# MyTouchPad.net
KiCad netlist of a schematic drawn in EasyEDA Pro
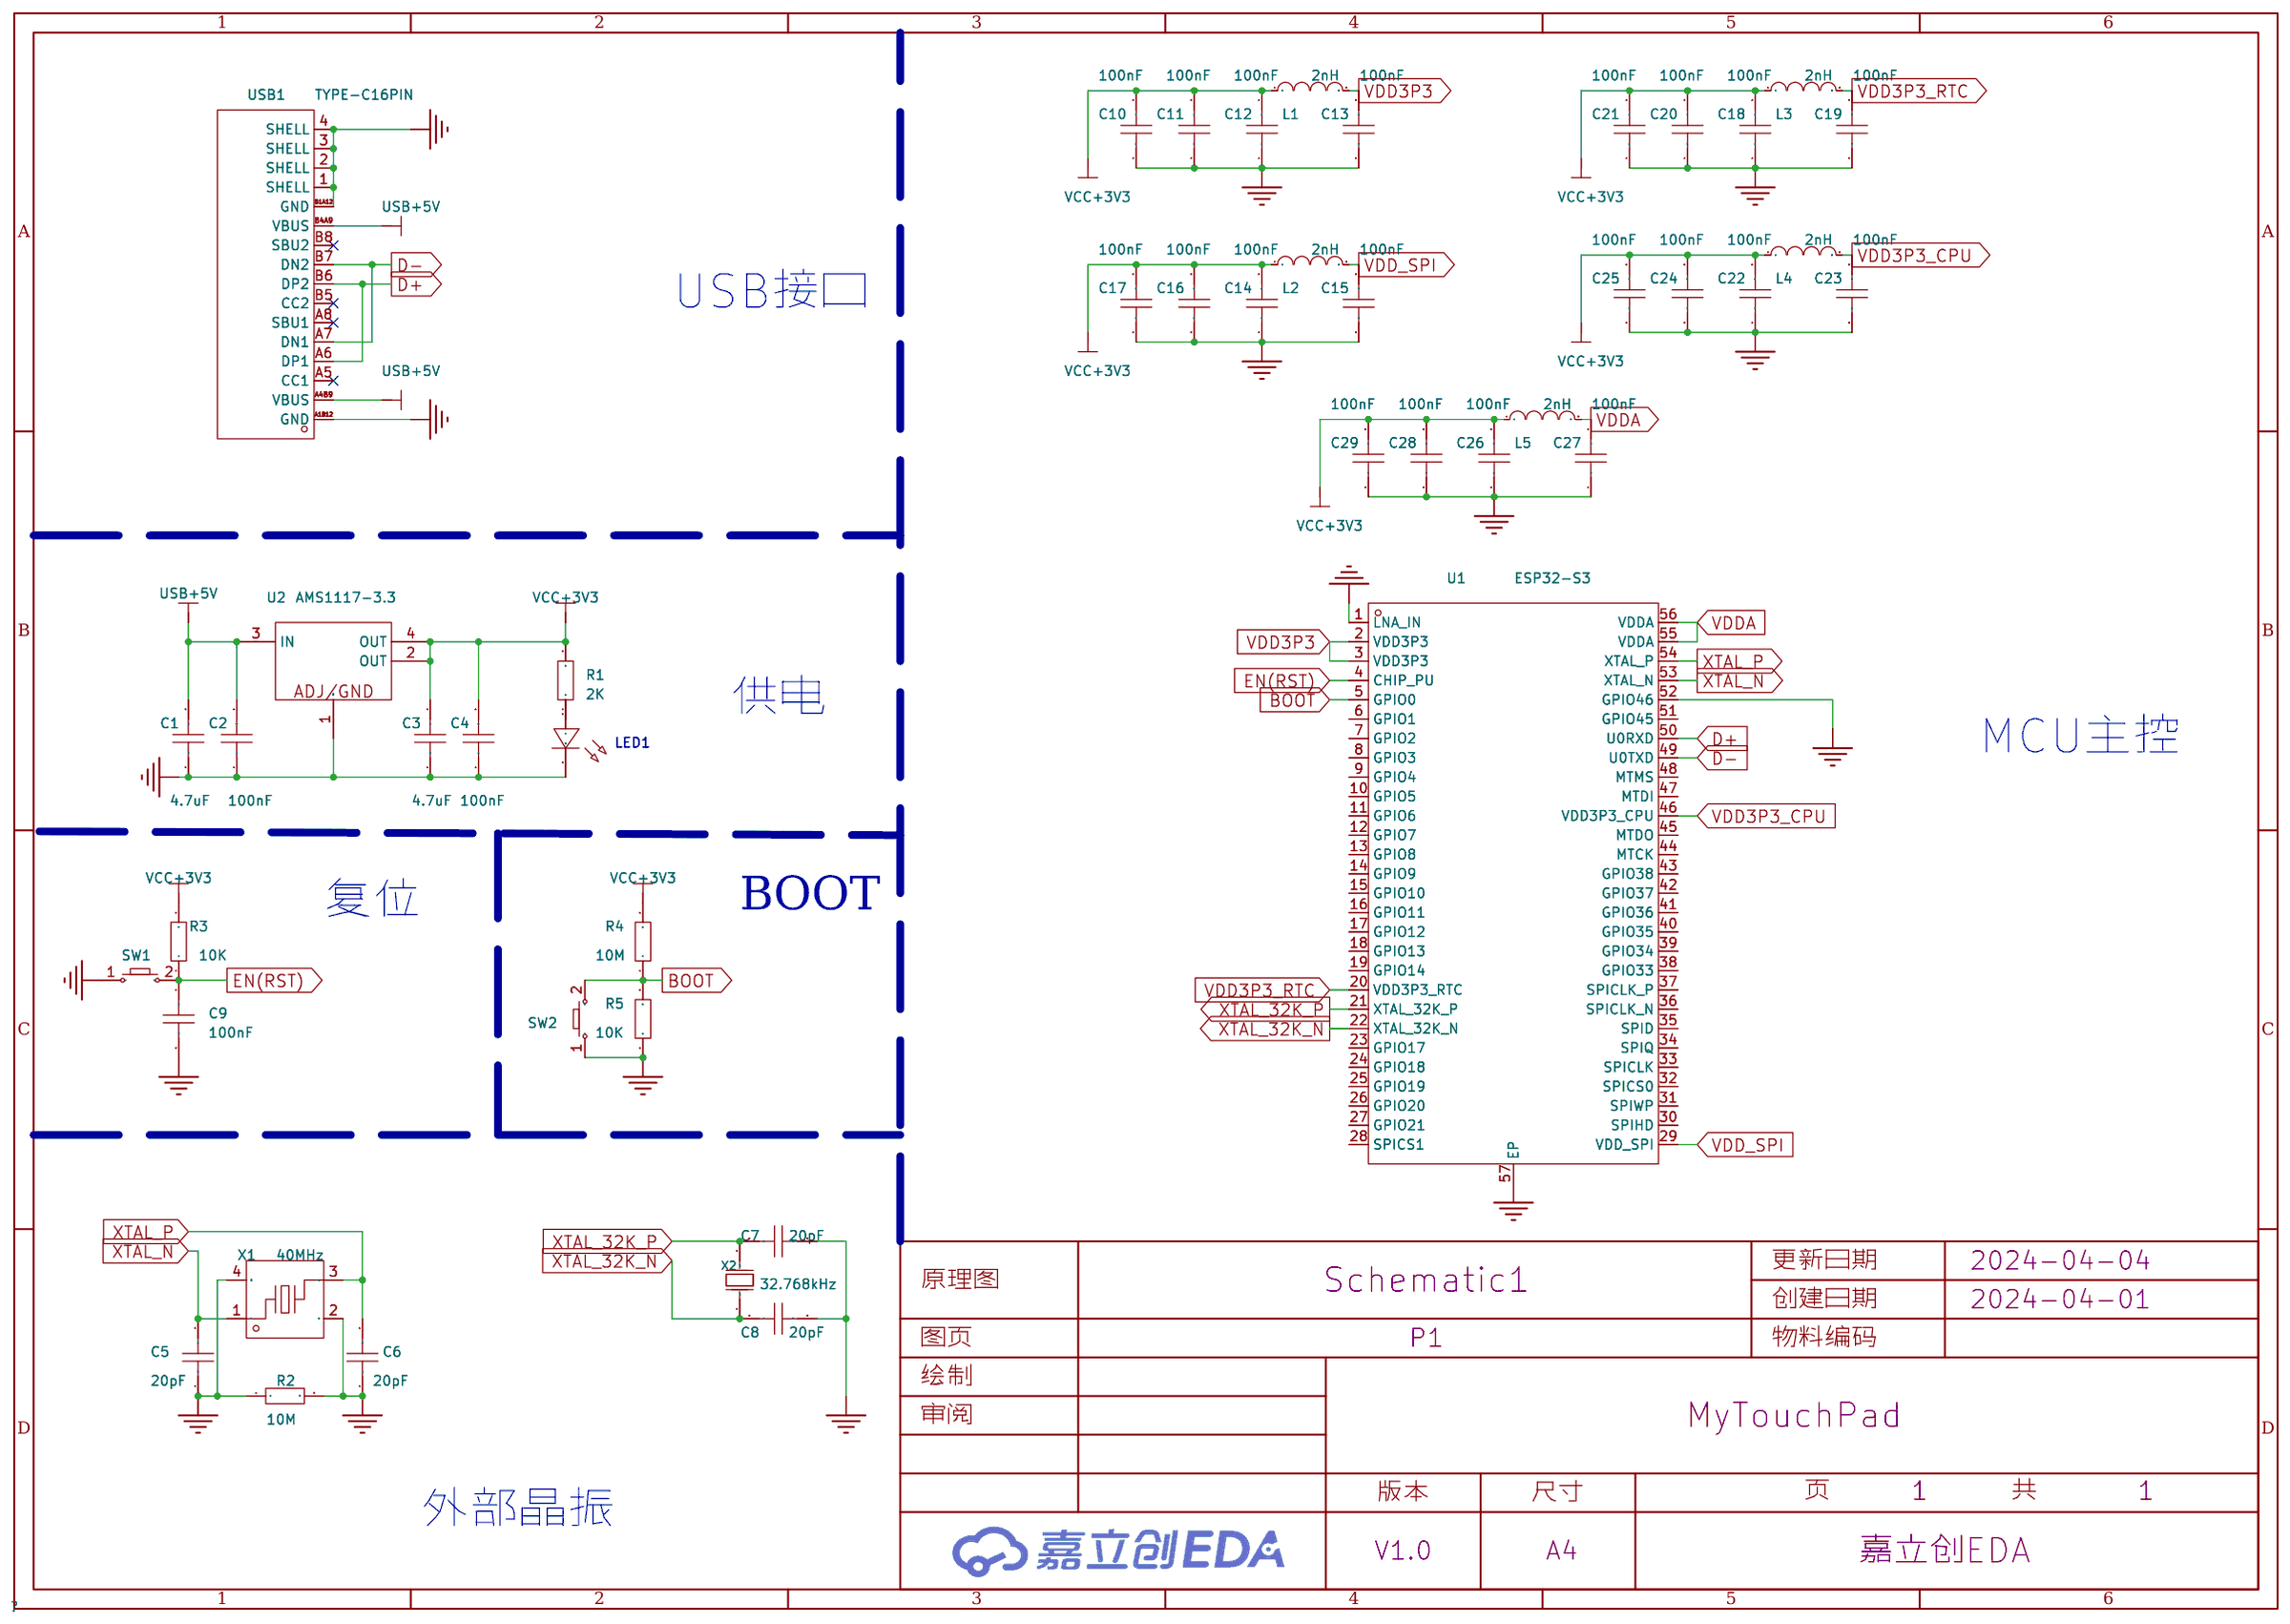
[diagram p0: schematic sheet]

(export (version "E")
  (design (tool "Eeschema 10.0.6"))
  (components
    (comp (ref "C1")
      (value "4.7uF")
      (footprint "easyedapro:C0603")
      (libsource (lib "easyedapro") (part "CapAcitance"))
    )
    (comp (ref "C2")
      (value "100nF")
      (footprint "easyedapro:C0603")
      (libsource (lib "easyedapro") (part "CapAcitance"))
    )
    (comp (ref "C3")
      (value "4.7uF")
      (footprint "easyedapro:C0603")
      (libsource (lib "easyedapro") (part "CapAcitance"))
    )
    (comp (ref "C4")
      (value "100nF")
      (footprint "easyedapro:C0603")
      (libsource (lib "easyedapro") (part "CapAcitance"))
    )
    (comp (ref "C5")
      (value "20pF")
      (footprint "easyedapro:C0603")
      (description "容值:20pF;精度:±2%;额定电压:50V;材质(温度系数):NP0;")
      (fields
        (field (name "Manufacturer Part") "CC0603GRNPO9BN200")
        (field (name "Manufacturer") "YAGEO(国巨)")
      )
      (libsource (lib "easyedapro") (part "CC0603GRNPO9BN200"))
    )
    (comp (ref "C6")
      (value "20pF")
      (footprint "easyedapro:C0603")
      (description "容值:20pF;精度:±2%;额定电压:50V;材质(温度系数):NP0;")
      (fields
        (field (name "Manufacturer Part") "CC0603GRNPO9BN200")
        (field (name "Manufacturer") "YAGEO(国巨)")
      )
      (libsource (lib "easyedapro") (part "CC0603GRNPO9BN200"))
    )
    (comp (ref "C7")
      (value "20pF")
      (footprint "easyedapro:C0603")
      (libsource (lib "easyedapro") (part "CapAcitance"))
    )
    (comp (ref "C8")
      (value "20pF")
      (footprint "easyedapro:C0603")
      (libsource (lib "easyedapro") (part "CapAcitance"))
    )
    (comp (ref "C9")
      (value "100nF")
      (footprint "easyedapro:C0603")
      (libsource (lib "easyedapro") (part "CapAcitance"))
    )
    (comp (ref "C10")
      (value "100nF")
      (footprint "easyedapro:C0603")
      (libsource (lib "easyedapro") (part "CapAcitance"))
    )
    (comp (ref "C11")
      (value "100nF")
      (footprint "easyedapro:C0603")
      (libsource (lib "easyedapro") (part "CapAcitance"))
    )
    (comp (ref "C12")
      (value "100nF")
      (footprint "easyedapro:C0603")
      (libsource (lib "easyedapro") (part "CapAcitance"))
    )
    (comp (ref "C13")
      (value "100nF")
      (footprint "easyedapro:C0603")
      (libsource (lib "easyedapro") (part "CapAcitance"))
    )
    (comp (ref "C14")
      (value "100nF")
      (footprint "easyedapro:C0603")
      (libsource (lib "easyedapro") (part "CapAcitance"))
    )
    (comp (ref "C15")
      (value "100nF")
      (footprint "easyedapro:C0603")
      (libsource (lib "easyedapro") (part "CapAcitance"))
    )
    (comp (ref "C16")
      (value "100nF")
      (footprint "easyedapro:C0603")
      (libsource (lib "easyedapro") (part "CapAcitance"))
    )
    (comp (ref "C17")
      (value "100nF")
      (footprint "easyedapro:C0603")
      (libsource (lib "easyedapro") (part "CapAcitance"))
    )
    (comp (ref "C18")
      (value "100nF")
      (footprint "easyedapro:C0603")
      (libsource (lib "easyedapro") (part "CapAcitance"))
    )
    (comp (ref "C19")
      (value "100nF")
      (footprint "easyedapro:C0603")
      (libsource (lib "easyedapro") (part "CapAcitance"))
    )
    (comp (ref "C20")
      (value "100nF")
      (footprint "easyedapro:C0603")
      (libsource (lib "easyedapro") (part "CapAcitance"))
    )
    (comp (ref "C21")
      (value "100nF")
      (footprint "easyedapro:C0603")
      (libsource (lib "easyedapro") (part "CapAcitance"))
    )
    (comp (ref "C22")
      (value "100nF")
      (footprint "easyedapro:C0603")
      (libsource (lib "easyedapro") (part "CapAcitance"))
    )
    (comp (ref "C23")
      (value "100nF")
      (footprint "easyedapro:C0603")
      (libsource (lib "easyedapro") (part "CapAcitance"))
    )
    (comp (ref "C24")
      (value "100nF")
      (footprint "easyedapro:C0603")
      (libsource (lib "easyedapro") (part "CapAcitance"))
    )
    (comp (ref "C25")
      (value "100nF")
      (footprint "easyedapro:C0603")
      (libsource (lib "easyedapro") (part "CapAcitance"))
    )
    (comp (ref "C26")
      (value "100nF")
      (footprint "easyedapro:C0603")
      (libsource (lib "easyedapro") (part "CapAcitance"))
    )
    (comp (ref "C27")
      (value "100nF")
      (footprint "easyedapro:C0603")
      (libsource (lib "easyedapro") (part "CapAcitance"))
    )
    (comp (ref "C28")
      (value "100nF")
      (footprint "easyedapro:C0603")
      (libsource (lib "easyedapro") (part "CapAcitance"))
    )
    (comp (ref "C29")
      (value "100nF")
      (footprint "easyedapro:C0603")
      (libsource (lib "easyedapro") (part "CapAcitance"))
    )
    (comp (ref "L1")
      (value "2nH")
      (footprint "easyedapro:L0603")
      (libsource (lib "easyedapro") (part "SDFL1608S100KTF"))
    )
    (comp (ref "L2")
      (value "2nH")
      (footprint "easyedapro:L0603")
      (libsource (lib "easyedapro") (part "SDFL1608S100KTF"))
    )
    (comp (ref "L3")
      (value "2nH")
      (footprint "easyedapro:L0603")
      (libsource (lib "easyedapro") (part "SDFL1608S100KTF"))
    )
    (comp (ref "L4")
      (value "2nH")
      (footprint "easyedapro:L0603")
      (libsource (lib "easyedapro") (part "SDFL1608S100KTF"))
    )
    (comp (ref "L5")
      (value "2nH")
      (footprint "easyedapro:L0603")
      (libsource (lib "easyedapro") (part "SDFL1608S100KTF"))
    )
    (comp (ref "LED1")
      (value "~")
      (footprint "easyedapro:LED_0603")
      (libsource (lib "easyedapro") (part "LED_G"))
    )
    (comp (ref "R1") (value "2K") (footprint "easyedapro:R0603") (libsource (lib "easyedapro") (part "电阻")))
    (comp (ref "R2") (value "10M") (footprint "easyedapro:R0603") (libsource (lib "easyedapro") (part "电阻")))
    (comp (ref "R3") (value "10K") (footprint "easyedapro:R0603") (libsource (lib "easyedapro") (part "电阻")))
    (comp (ref "R4") (value "10M") (footprint "easyedapro:R0603") (libsource (lib "easyedapro") (part "电阻")))
    (comp (ref "R5") (value "10K") (footprint "easyedapro:R0603") (libsource (lib "easyedapro") (part "电阻")))
    (comp (ref "SW1")
      (value "~")
      (footprint "easyedapro:Key_SMD_3x4x2")
      (libsource (lib "easyedapro") (part "轻触按键x2"))
    )
    (comp (ref "SW2")
      (value "~")
      (footprint "easyedapro:Key_SMD_3x4x2")
      (libsource (lib "easyedapro") (part "轻触按键x2"))
    )
    (comp (ref "U1")
      (value "ESP32-S3")
      (footprint "easyedapro:QFN-56_L7.0-W7.0-P0.40-TL-EP4.0")
      (fields (field (name "Manufacturer") "ESPRESSIF(乐鑫)"))
      (libsource (lib "easyedapro") (part "ESP32-S3"))
    )
    (comp (ref "U2")
      (value "AMS1117-3.3")
      (footprint "easyedapro:SOT-223-3_L6.4-W3.5-P2.30-LS7.0-BR")
      (fields (field (name "Manufacturer") "国芯佳品"))
      (libsource (lib "easyedapro") (part "AMS1117-3.3_C2992570"))
    )
    (comp (ref "USB1")
      (value "TYPE-C16PIN")
      (footprint "easyedapro:USB-C-SMD_TYPE-C16PIN")
      (description "连接器类型:Type-C;标准:-;公母:母;端口数量:1;触点数量:16P;安装方式:卧贴;额定电流 - 电源:3A;工作温度范围:-40°C~+85°C;")
      (fields (field (name "Manufacturer") "SHOU HAN(首韩)"))
      (libsource (lib "easyedapro") (part "TYPE-C16PIN"))
    )
    (comp (ref "X1")
      (value "40MHz")
      (footprint "easyedapro:CRYSTAL-SMD_4P-L2.5-W2.0-BL")
      (description "晶振类型:贴片晶振;频率:40MHz;常温频差:±10ppm;外接负载电容:9pF;")
      (fields (field (name "Manufacturer Part") "S2240000091050JY") (field (name "Manufacturer") "JGHC(晶光华)"))
      (libsource (lib "easyedapro") (part "S2240000091050JY"))
    )
    (comp (ref "X2")
      (value "32.768kHz")
      (footprint "easyedapro:CRYSTAL-SMD_L3.2-W1.5-2")
      (description "频率:32.768kHz;常温频差:±20ppm;外接负载电容:6pF;频率稳定度(全温):-;")
      (fields
        (field (name "Manufacturer Part") "ABS07-32.768KHZ-6-T")
        (field (name "Manufacturer") "ABRACON")
      )
      (libsource (lib "easyedapro") (part "ABS07-32.768KHZ-6-T"))
    )
  )
  (nets
    (net (code "1") (name "BOOT") (class "Default")
      (node (ref "R4") (pin "1") (pinfunction "1_1") (pintype "input"))
      (node (ref "R5") (pin "2") (pinfunction "2_2") (pintype "input"))
      (node (ref "SW2") (pin "2") (pinfunction "2_2") (pintype "input"))
      (node (ref "U1") (pin "5") (pinfunction "GPIO0_5") (pintype "unspecified"))
    )
    (net (code "2") (name "D+") (class "Default")
      (node (ref "U1") (pin "50") (pinfunction "U0RXD_50") (pintype "unspecified"))
      (node (ref "USB1") (pin "A6") (pinfunction "DP1_A6") (pintype "unspecified"))
      (node (ref "USB1") (pin "B6") (pinfunction "DP2_B6") (pintype "unspecified"))
    )
    (net (code "3") (name "D-") (class "Default")
      (node (ref "U1") (pin "49") (pinfunction "U0TXD_49") (pintype "unspecified"))
      (node (ref "USB1") (pin "A7") (pinfunction "DN1_A7") (pintype "unspecified"))
      (node (ref "USB1") (pin "B7") (pinfunction "DN2_B7") (pintype "unspecified"))
    )
    (net (code "4") (name "EN(RST)") (class "Default")
      (node (ref "C9") (pin "1") (pinfunction "1_1") (pintype "input"))
      (node (ref "R3") (pin "1") (pinfunction "1_1") (pintype "input"))
      (node (ref "SW1") (pin "2") (pinfunction "2_2") (pintype "input"))
      (node (ref "U1") (pin "4") (pinfunction "CHIP_PU_4") (pintype "unspecified"))
    )
    (net (code "5") (name "GND") (class "Default")
      (node (ref "C1") (pin "1") (pinfunction "1_1") (pintype "input"))
      (node (ref "C10") (pin "1") (pinfunction "1_1") (pintype "input"))
      (node (ref "C11") (pin "1") (pinfunction "1_1") (pintype "input"))
      (node (ref "C12") (pin "1") (pinfunction "1_1") (pintype "input"))
      (node (ref "C13") (pin "1") (pinfunction "1_1") (pintype "input"))
      (node (ref "C14") (pin "1") (pinfunction "1_1") (pintype "input"))
      (node (ref "C15") (pin "1") (pinfunction "1_1") (pintype "input"))
      (node (ref "C16") (pin "1") (pinfunction "1_1") (pintype "input"))
      (node (ref "C17") (pin "1") (pinfunction "1_1") (pintype "input"))
      (node (ref "C18") (pin "1") (pinfunction "1_1") (pintype "input"))
      (node (ref "C19") (pin "1") (pinfunction "1_1") (pintype "input"))
      (node (ref "C2") (pin "1") (pinfunction "1_1") (pintype "input"))
      (node (ref "C20") (pin "1") (pinfunction "1_1") (pintype "input"))
      (node (ref "C21") (pin "1") (pinfunction "1_1") (pintype "input"))
      (node (ref "C22") (pin "1") (pinfunction "1_1") (pintype "input"))
      (node (ref "C23") (pin "1") (pinfunction "1_1") (pintype "input"))
      (node (ref "C24") (pin "1") (pinfunction "1_1") (pintype "input"))
      (node (ref "C25") (pin "1") (pinfunction "1_1") (pintype "input"))
      (node (ref "C26") (pin "1") (pinfunction "1_1") (pintype "input"))
      (node (ref "C27") (pin "1") (pinfunction "1_1") (pintype "input"))
      (node (ref "C28") (pin "1") (pinfunction "1_1") (pintype "input"))
      (node (ref "C29") (pin "1") (pinfunction "1_1") (pintype "input"))
      (node (ref "C3") (pin "1") (pinfunction "1_1") (pintype "input"))
      (node (ref "C4") (pin "1") (pinfunction "1_1") (pintype "input"))
      (node (ref "C5") (pin "1") (pinfunction "1_1") (pintype "unspecified"))
      (node (ref "C6") (pin "1") (pinfunction "1_1") (pintype "unspecified"))
      (node (ref "C7") (pin "2") (pinfunction "2_2") (pintype "input"))
      (node (ref "C8") (pin "2") (pinfunction "2_2") (pintype "input"))
      (node (ref "C9") (pin "2") (pinfunction "2_2") (pintype "input"))
      (node (ref "LED1") (pin "1") (pinfunction "C_1") (pintype "input"))
      (node (ref "R2") (pin "1") (pinfunction "1_1") (pintype "input"))
      (node (ref "R2") (pin "2") (pinfunction "2_2") (pintype "input"))
      (node (ref "R5") (pin "1") (pinfunction "1_1") (pintype "input"))
      (node (ref "SW1") (pin "1") (pinfunction "1_1") (pintype "input"))
      (node (ref "SW2") (pin "1") (pinfunction "1_1") (pintype "input"))
      (node (ref "U1") (pin "1") (pinfunction "LNA_IN_1") (pintype "unspecified"))
      (node (ref "U1") (pin "52") (pinfunction "GPIO46_52") (pintype "unspecified"))
      (node (ref "U1") (pin "57") (pinfunction "EP_57") (pintype "unspecified"))
      (node (ref "U2") (pin "1") (pinfunction "ADJ/GND_1") (pintype "unspecified"))
      (node (ref "USB1") (pin "1") (pinfunction "SHELL_1") (pintype "unspecified"))
      (node (ref "USB1") (pin "2") (pinfunction "SHELL_2") (pintype "unspecified"))
      (node (ref "USB1") (pin "3") (pinfunction "SHELL_3") (pintype "unspecified"))
      (node (ref "USB1") (pin "4") (pinfunction "SHELL_4") (pintype "unspecified"))
      (node (ref "USB1") (pin "A1B12") (pinfunction "GND_A1B12") (pintype "unspecified"))
      (node (ref "USB1") (pin "B1A12") (pinfunction "GND_B1A12") (pintype "unspecified"))
      (node (ref "X1") (pin "2") (pinfunction "GND_2") (pintype "input"))
      (node (ref "X1") (pin "4") (pinfunction "GND_4") (pintype "input"))
    )
    (net (code "6") (name "Net-(LED1-A)") (class "Default")
      (node (ref "LED1") (pin "2") (pinfunction "A_2") (pintype "input"))
      (node (ref "R1") (pin "1") (pinfunction "1_1") (pintype "input"))
    )
    (net (code "7") (name "USB+5V") (class "Default")
      (node (ref "C1") (pin "2") (pinfunction "2_2") (pintype "input"))
      (node (ref "C2") (pin "2") (pinfunction "2_2") (pintype "input"))
      (node (ref "U2") (pin "3") (pinfunction "IN_3") (pintype "unspecified"))
      (node (ref "USB1") (pin "A4B9") (pinfunction "VBUS_A4B9") (pintype "unspecified"))
      (node (ref "USB1") (pin "B4A9") (pinfunction "VBUS_B4A9") (pintype "unspecified"))
    )
    (net (code "8") (name "VCC+3V3") (class "Default")
      (node (ref "C10") (pin "2") (pinfunction "2_2") (pintype "input"))
      (node (ref "C11") (pin "2") (pinfunction "2_2") (pintype "input"))
      (node (ref "C12") (pin "2") (pinfunction "2_2") (pintype "input"))
      (node (ref "C14") (pin "2") (pinfunction "2_2") (pintype "input"))
      (node (ref "C16") (pin "2") (pinfunction "2_2") (pintype "input"))
      (node (ref "C17") (pin "2") (pinfunction "2_2") (pintype "input"))
      (node (ref "C18") (pin "2") (pinfunction "2_2") (pintype "input"))
      (node (ref "C20") (pin "2") (pinfunction "2_2") (pintype "input"))
      (node (ref "C21") (pin "2") (pinfunction "2_2") (pintype "input"))
      (node (ref "C22") (pin "2") (pinfunction "2_2") (pintype "input"))
      (node (ref "C24") (pin "2") (pinfunction "2_2") (pintype "input"))
      (node (ref "C25") (pin "2") (pinfunction "2_2") (pintype "input"))
      (node (ref "C26") (pin "2") (pinfunction "2_2") (pintype "input"))
      (node (ref "C28") (pin "2") (pinfunction "2_2") (pintype "input"))
      (node (ref "C29") (pin "2") (pinfunction "2_2") (pintype "input"))
      (node (ref "C3") (pin "2") (pinfunction "2_2") (pintype "input"))
      (node (ref "C4") (pin "2") (pinfunction "2_2") (pintype "input"))
      (node (ref "L1") (pin "1") (pinfunction "1_1") (pintype "unspecified"))
      (node (ref "L2") (pin "1") (pinfunction "1_1") (pintype "unspecified"))
      (node (ref "L3") (pin "1") (pinfunction "1_1") (pintype "unspecified"))
      (node (ref "L4") (pin "1") (pinfunction "1_1") (pintype "unspecified"))
      (node (ref "L5") (pin "1") (pinfunction "1_1") (pintype "unspecified"))
      (node (ref "R1") (pin "2") (pinfunction "2_2") (pintype "input"))
      (node (ref "R3") (pin "2") (pinfunction "2_2") (pintype "input"))
      (node (ref "R4") (pin "2") (pinfunction "2_2") (pintype "input"))
      (node (ref "U2") (pin "2") (pinfunction "OUT_2") (pintype "unspecified"))
      (node (ref "U2") (pin "4") (pinfunction "OUT_4") (pintype "unspecified"))
    )
    (net (code "9") (name "VDD3P3") (class "Default")
      (node (ref "C13") (pin "2") (pinfunction "2_2") (pintype "input"))
      (node (ref "L1") (pin "2") (pinfunction "2_2") (pintype "unspecified"))
      (node (ref "U1") (pin "2") (pinfunction "VDD3P3_2") (pintype "unspecified"))
      (node (ref "U1") (pin "3") (pinfunction "VDD3P3_3") (pintype "unspecified"))
    )
    (net (code "10") (name "VDD3P3_CPU") (class "Default")
      (node (ref "C23") (pin "2") (pinfunction "2_2") (pintype "input"))
      (node (ref "L4") (pin "2") (pinfunction "2_2") (pintype "unspecified"))
      (node (ref "U1") (pin "46") (pinfunction "VDD3P3_CPU_46") (pintype "unspecified"))
    )
    (net (code "11") (name "VDD3P3_RTC") (class "Default")
      (node (ref "C19") (pin "2") (pinfunction "2_2") (pintype "input"))
      (node (ref "L3") (pin "2") (pinfunction "2_2") (pintype "unspecified"))
      (node (ref "U1") (pin "20") (pinfunction "VDD3P3_RTC_20") (pintype "unspecified"))
    )
    (net (code "12") (name "VDDA") (class "Default")
      (node (ref "C27") (pin "2") (pinfunction "2_2") (pintype "input"))
      (node (ref "L5") (pin "2") (pinfunction "2_2") (pintype "unspecified"))
      (node (ref "U1") (pin "55") (pinfunction "VDDA_55") (pintype "unspecified"))
      (node (ref "U1") (pin "56") (pinfunction "VDDA_56") (pintype "unspecified"))
    )
    (net (code "13") (name "VDD_SPI") (class "Default")
      (node (ref "C15") (pin "2") (pinfunction "2_2") (pintype "input"))
      (node (ref "L2") (pin "2") (pinfunction "2_2") (pintype "unspecified"))
      (node (ref "U1") (pin "29") (pinfunction "VDD_SPI_29") (pintype "unspecified"))
    )
    (net (code "14") (name "XTAL_32K_N") (class "Default")
      (node (ref "C8") (pin "1") (pinfunction "1_1") (pintype "input"))
      (node (ref "U1") (pin "22") (pinfunction "XTAL_32K_N_22") (pintype "unspecified"))
      (node (ref "X2") (pin "1") (pinfunction "OSC1_1") (pintype "input"))
    )
    (net (code "15") (name "XTAL_32K_P") (class "Default")
      (node (ref "C7") (pin "1") (pinfunction "1_1") (pintype "input"))
      (node (ref "U1") (pin "21") (pinfunction "XTAL_32K_P_21") (pintype "unspecified"))
      (node (ref "X2") (pin "2") (pinfunction "OSC2_2") (pintype "input"))
    )
    (net (code "16") (name "XTAL_N") (class "Default")
      (node (ref "C5") (pin "2") (pinfunction "2_2") (pintype "unspecified"))
      (node (ref "U1") (pin "53") (pinfunction "XTAL_N_53") (pintype "unspecified"))
      (node (ref "X1") (pin "1") (pinfunction "1_1") (pintype "input"))
    )
    (net (code "17") (name "XTAL_P") (class "Default")
      (node (ref "C6") (pin "2") (pinfunction "2_2") (pintype "unspecified"))
      (node (ref "U1") (pin "54") (pinfunction "XTAL_P_54") (pintype "unspecified"))
      (node (ref "X1") (pin "3") (pinfunction "3_3") (pintype "input"))
    )
    (net (code "18") (name "unconnected-(U1-GPIO1-Pad6)") (class "Default")
      (node (ref "U1") (pin "6") (pinfunction "GPIO1_6") (pintype "unspecified"))
    )
    (net (code "19") (name "unconnected-(U1-GPIO2-Pad7)") (class "Default")
      (node (ref "U1") (pin "7") (pinfunction "GPIO2_7") (pintype "unspecified"))
    )
    (net (code "20") (name "unconnected-(U1-GPIO3-Pad8)") (class "Default")
      (node (ref "U1") (pin "8") (pinfunction "GPIO3_8") (pintype "unspecified"))
    )
    (net (code "21") (name "unconnected-(U1-GPIO4-Pad9)") (class "Default")
      (node (ref "U1") (pin "9") (pinfunction "GPIO4_9") (pintype "unspecified"))
    )
    (net (code "22") (name "unconnected-(U1-GPIO5-Pad10)") (class "Default")
      (node (ref "U1") (pin "10") (pinfunction "GPIO5_10") (pintype "unspecified"))
    )
    (net (code "23") (name "unconnected-(U1-GPIO6-Pad11)") (class "Default")
      (node (ref "U1") (pin "11") (pinfunction "GPIO6_11") (pintype "unspecified"))
    )
    (net (code "24") (name "unconnected-(U1-GPIO7-Pad12)") (class "Default")
      (node (ref "U1") (pin "12") (pinfunction "GPIO7_12") (pintype "unspecified"))
    )
    (net (code "25") (name "unconnected-(U1-GPIO8-Pad13)") (class "Default")
      (node (ref "U1") (pin "13") (pinfunction "GPIO8_13") (pintype "unspecified"))
    )
    (net (code "26") (name "unconnected-(U1-GPIO9-Pad14)") (class "Default")
      (node (ref "U1") (pin "14") (pinfunction "GPIO9_14") (pintype "unspecified"))
    )
    (net (code "27") (name "unconnected-(U1-GPIO10-Pad15)") (class "Default")
      (node (ref "U1") (pin "15") (pinfunction "GPIO10_15") (pintype "unspecified"))
    )
    (net (code "28") (name "unconnected-(U1-GPIO11-Pad16)") (class "Default")
      (node (ref "U1") (pin "16") (pinfunction "GPIO11_16") (pintype "unspecified"))
    )
    (net (code "29") (name "unconnected-(U1-GPIO12-Pad17)") (class "Default")
      (node (ref "U1") (pin "17") (pinfunction "GPIO12_17") (pintype "unspecified"))
    )
    (net (code "30") (name "unconnected-(U1-GPIO13-Pad18)") (class "Default")
      (node (ref "U1") (pin "18") (pinfunction "GPIO13_18") (pintype "unspecified"))
    )
    (net (code "31") (name "unconnected-(U1-GPIO14-Pad19)") (class "Default")
      (node (ref "U1") (pin "19") (pinfunction "GPIO14_19") (pintype "unspecified"))
    )
    (net (code "32") (name "unconnected-(U1-GPIO17-Pad23)") (class "Default")
      (node (ref "U1") (pin "23") (pinfunction "GPIO17_23") (pintype "unspecified"))
    )
    (net (code "33") (name "unconnected-(U1-GPIO18-Pad24)") (class "Default")
      (node (ref "U1") (pin "24") (pinfunction "GPIO18_24") (pintype "unspecified"))
    )
    (net (code "34") (name "unconnected-(U1-GPIO19-Pad25)") (class "Default")
      (node (ref "U1") (pin "25") (pinfunction "GPIO19_25") (pintype "unspecified"))
    )
    (net (code "35") (name "unconnected-(U1-GPIO20-Pad26)") (class "Default")
      (node (ref "U1") (pin "26") (pinfunction "GPIO20_26") (pintype "unspecified"))
    )
    (net (code "36") (name "unconnected-(U1-GPIO21-Pad27)") (class "Default")
      (node (ref "U1") (pin "27") (pinfunction "GPIO21_27") (pintype "unspecified"))
    )
    (net (code "37") (name "unconnected-(U1-GPIO33-Pad38)") (class "Default")
      (node (ref "U1") (pin "38") (pinfunction "GPIO33_38") (pintype "unspecified"))
    )
    (net (code "38") (name "unconnected-(U1-GPIO34-Pad39)") (class "Default")
      (node (ref "U1") (pin "39") (pinfunction "GPIO34_39") (pintype "unspecified"))
    )
    (net (code "39") (name "unconnected-(U1-GPIO35-Pad40)") (class "Default")
      (node (ref "U1") (pin "40") (pinfunction "GPIO35_40") (pintype "unspecified"))
    )
    (net (code "40") (name "unconnected-(U1-GPIO36-Pad41)") (class "Default")
      (node (ref "U1") (pin "41") (pinfunction "GPIO36_41") (pintype "unspecified"))
    )
    (net (code "41") (name "unconnected-(U1-GPIO37-Pad42)") (class "Default")
      (node (ref "U1") (pin "42") (pinfunction "GPIO37_42") (pintype "unspecified"))
    )
    (net (code "42") (name "unconnected-(U1-GPIO38-Pad43)") (class "Default")
      (node (ref "U1") (pin "43") (pinfunction "GPIO38_43") (pintype "unspecified"))
    )
    (net (code "43") (name "unconnected-(U1-GPIO45-Pad51)") (class "Default")
      (node (ref "U1") (pin "51") (pinfunction "GPIO45_51") (pintype "unspecified"))
    )
    (net (code "44") (name "unconnected-(U1-MTCK-Pad44)") (class "Default")
      (node (ref "U1") (pin "44") (pinfunction "MTCK_44") (pintype "unspecified"))
    )
    (net (code "45") (name "unconnected-(U1-MTDI-Pad47)") (class "Default")
      (node (ref "U1") (pin "47") (pinfunction "MTDI_47") (pintype "unspecified"))
    )
    (net (code "46") (name "unconnected-(U1-MTDO-Pad45)") (class "Default")
      (node (ref "U1") (pin "45") (pinfunction "MTDO_45") (pintype "unspecified"))
    )
    (net (code "47") (name "unconnected-(U1-MTMS-Pad48)") (class "Default")
      (node (ref "U1") (pin "48") (pinfunction "MTMS_48") (pintype "unspecified"))
    )
    (net (code "48") (name "unconnected-(U1-SPICLK-Pad33)") (class "Default")
      (node (ref "U1") (pin "33") (pinfunction "SPICLK_33") (pintype "unspecified"))
    )
    (net (code "49") (name "unconnected-(U1-SPICLK_N-Pad36)") (class "Default")
      (node (ref "U1") (pin "36") (pinfunction "SPICLK_N_36") (pintype "unspecified"))
    )
    (net (code "50") (name "unconnected-(U1-SPICLK_P-Pad37)") (class "Default")
      (node (ref "U1") (pin "37") (pinfunction "SPICLK_P_37") (pintype "unspecified"))
    )
    (net (code "51") (name "unconnected-(U1-SPICS0-Pad32)") (class "Default")
      (node (ref "U1") (pin "32") (pinfunction "SPICS0_32") (pintype "unspecified"))
    )
    (net (code "52") (name "unconnected-(U1-SPICS1-Pad28)") (class "Default")
      (node (ref "U1") (pin "28") (pinfunction "SPICS1_28") (pintype "unspecified"))
    )
    (net (code "53") (name "unconnected-(U1-SPID-Pad35)") (class "Default")
      (node (ref "U1") (pin "35") (pinfunction "SPID_35") (pintype "unspecified"))
    )
    (net (code "54") (name "unconnected-(U1-SPIHD-Pad30)") (class "Default")
      (node (ref "U1") (pin "30") (pinfunction "SPIHD_30") (pintype "unspecified"))
    )
    (net (code "55") (name "unconnected-(U1-SPIQ-Pad34)") (class "Default")
      (node (ref "U1") (pin "34") (pinfunction "SPIQ_34") (pintype "unspecified"))
    )
    (net (code "56") (name "unconnected-(U1-SPIWP-Pad31)") (class "Default")
      (node (ref "U1") (pin "31") (pinfunction "SPIWP_31") (pintype "unspecified"))
    )
    (net (code "57") (name "unconnected-(USB1-CC1-PadA5)") (class "Default")
      (node (ref "USB1") (pin "A5") (pinfunction "CC1_A5") (pintype "unspecified+no_connect"))
    )
    (net (code "58") (name "unconnected-(USB1-CC2-PadB5)") (class "Default")
      (node (ref "USB1") (pin "B5") (pinfunction "CC2_B5") (pintype "unspecified+no_connect"))
    )
    (net (code "59") (name "unconnected-(USB1-SBU1-PadA8)") (class "Default")
      (node (ref "USB1") (pin "A8") (pinfunction "SBU1_A8") (pintype "unspecified+no_connect"))
    )
    (net (code "60") (name "unconnected-(USB1-SBU2-PadB8)") (class "Default")
      (node (ref "USB1") (pin "B8") (pinfunction "SBU2_B8") (pintype "unspecified+no_connect"))
    )
  )
)
